# speed_controllers.net
KiCad netlist of a schematic drawn in EAGLE
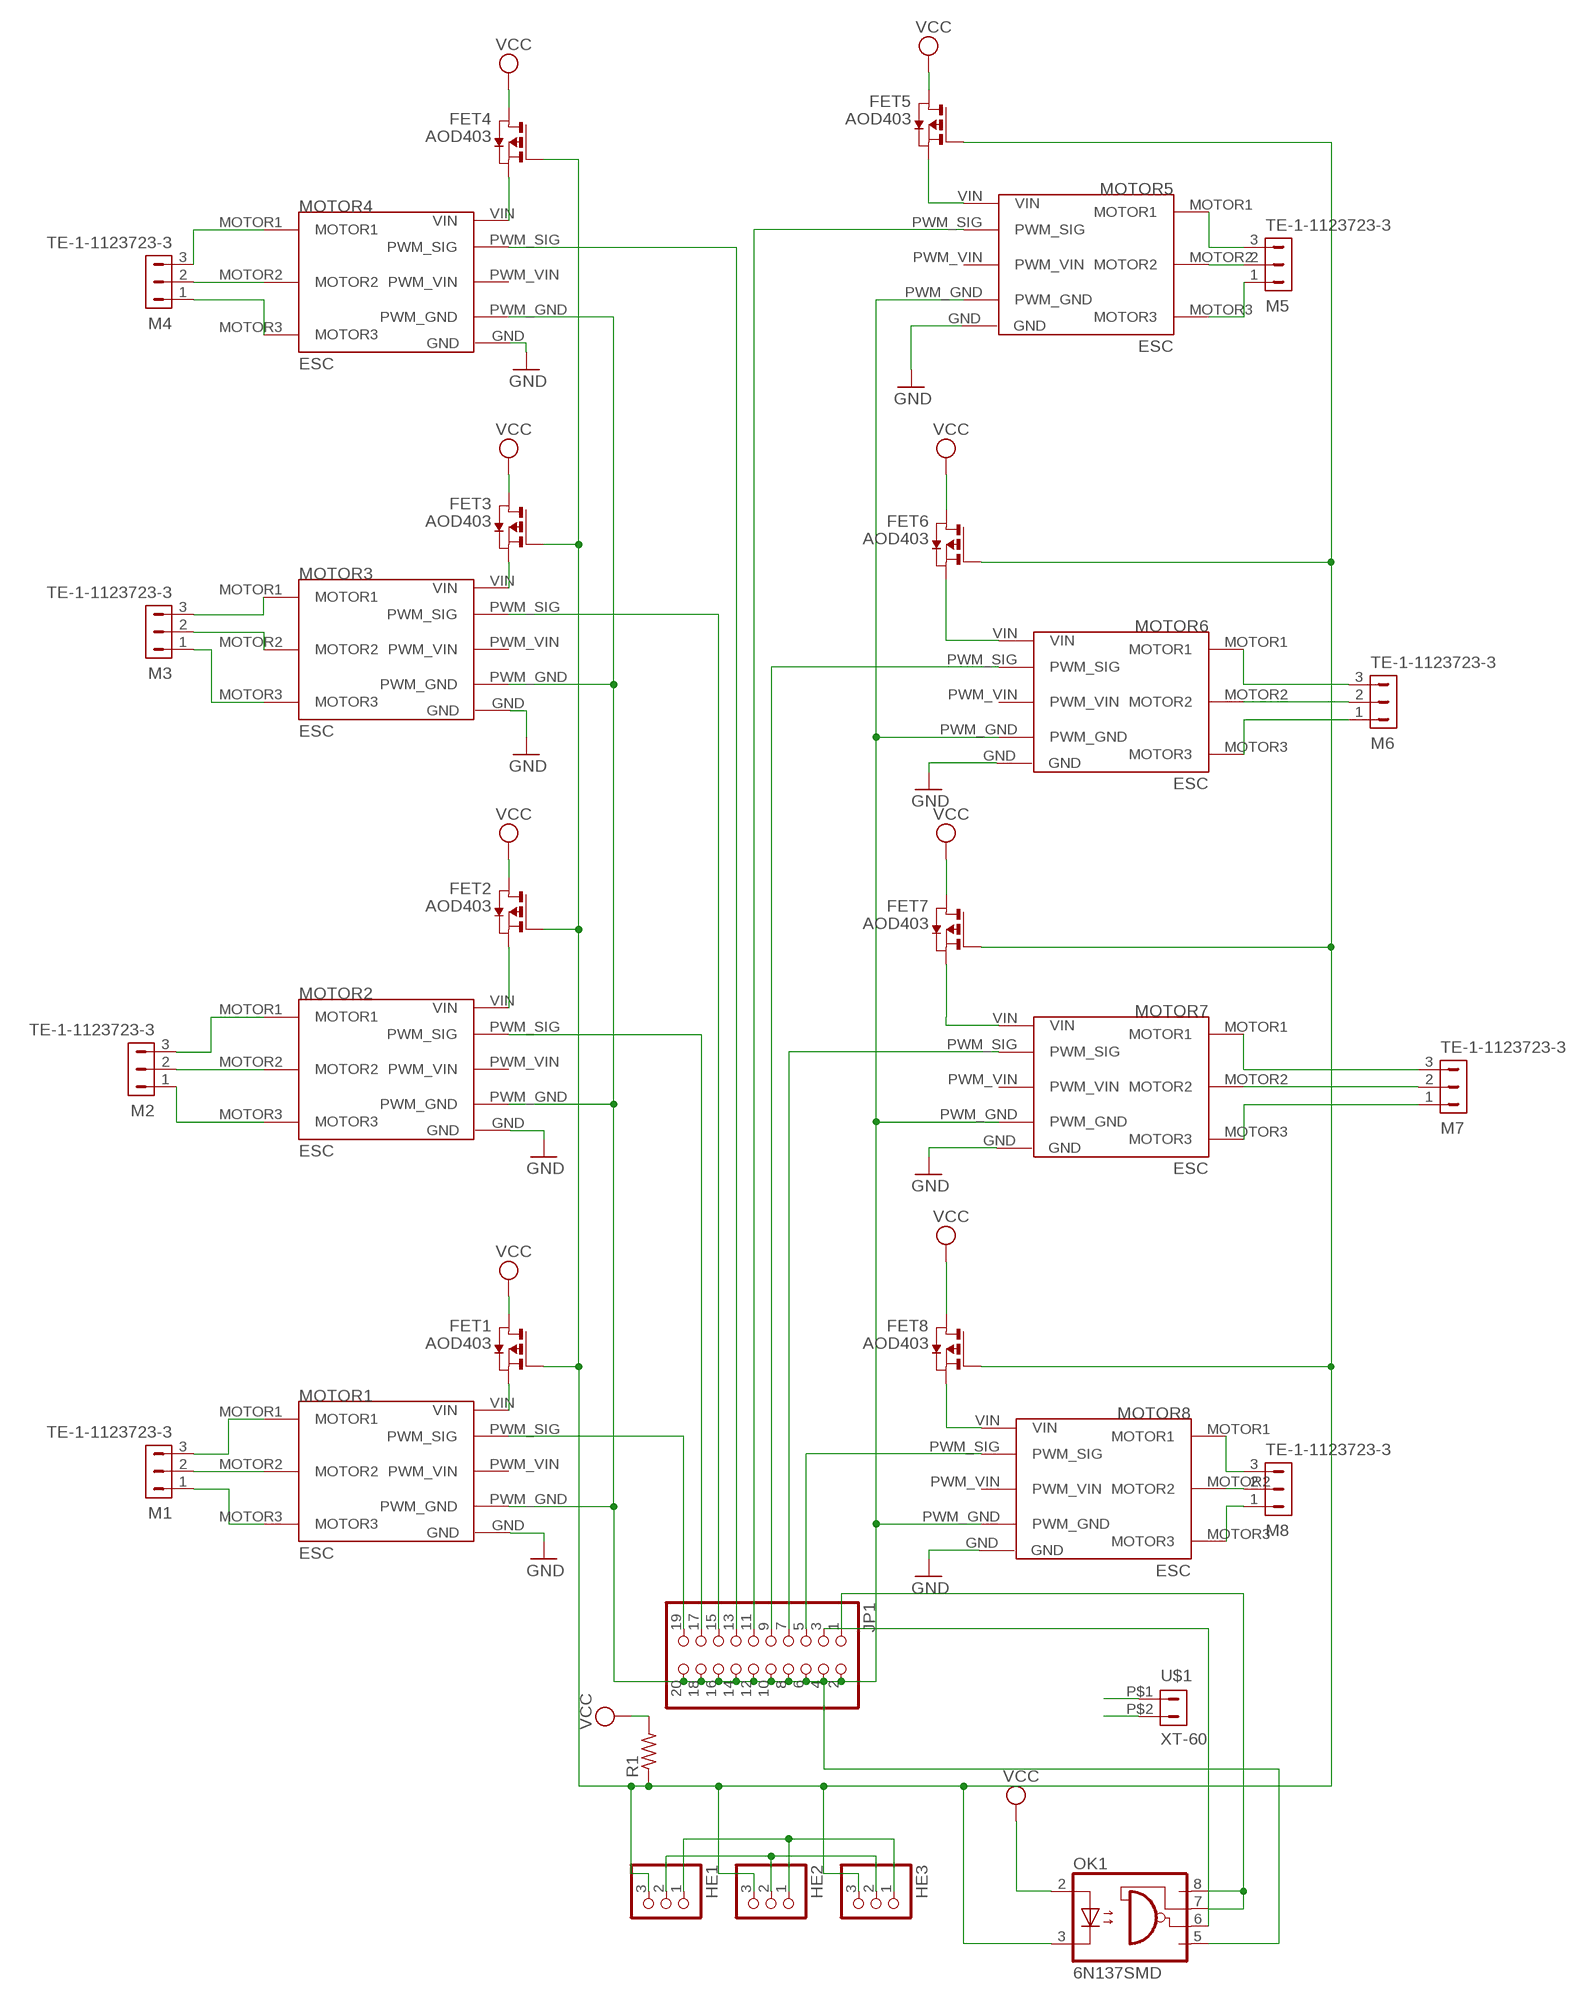
[diagram p0: schematic, sheet 1]

(export (version "E")
  (design (tool "Eeschema 10.0.6"))
  (components
    (comp (ref "FET1")
      (value "AOD403")
      (footprint "eagle-import:TO252")
      (libsource (lib "eagle-import") (part "AOD403"))
    )
    (comp (ref "FET2")
      (value "AOD403")
      (footprint "eagle-import:TO252")
      (libsource (lib "eagle-import") (part "AOD403"))
    )
    (comp (ref "FET3")
      (value "AOD403")
      (footprint "eagle-import:TO252")
      (libsource (lib "eagle-import") (part "AOD403"))
    )
    (comp (ref "FET4")
      (value "AOD403")
      (footprint "eagle-import:TO252")
      (libsource (lib "eagle-import") (part "AOD403"))
    )
    (comp (ref "FET5")
      (value "AOD403")
      (footprint "eagle-import:TO252")
      (libsource (lib "eagle-import") (part "AOD403"))
    )
    (comp (ref "FET6")
      (value "AOD403")
      (footprint "eagle-import:TO252")
      (libsource (lib "eagle-import") (part "AOD403"))
    )
    (comp (ref "FET7")
      (value "AOD403")
      (footprint "eagle-import:TO252")
      (libsource (lib "eagle-import") (part "AOD403"))
    )
    (comp (ref "FET8")
      (value "AOD403")
      (footprint "eagle-import:TO252")
      (libsource (lib "eagle-import") (part "AOD403"))
    )
    (comp (ref "HE1")
      (value "PINHD-1X3")
      (footprint "eagle-import:1X03")
      (libsource (lib "eagle-import") (part "PINHD-1X3"))
    )
    (comp (ref "HE2")
      (value "PINHD-1X3")
      (footprint "eagle-import:1X03")
      (libsource (lib "eagle-import") (part "PINHD-1X3"))
    )
    (comp (ref "HE3")
      (value "PINHD-1X3")
      (footprint "eagle-import:1X03")
      (libsource (lib "eagle-import") (part "PINHD-1X3"))
    )
    (comp (ref "JP1")
      (value "PINHD-2X10")
      (footprint "eagle-import:2X10")
      (libsource (lib "eagle-import") (part "PINHD-2X10"))
    )
    (comp (ref "M1")
      (value "TE-1-1123723-3")
      (footprint "eagle-import:TE-1-1123723-3")
      (libsource (lib "eagle-import") (part "TE-1-1123723-3"))
    )
    (comp (ref "M2")
      (value "TE-1-1123723-3")
      (footprint "eagle-import:TE-1-1123723-3")
      (libsource (lib "eagle-import") (part "TE-1-1123723-3"))
    )
    (comp (ref "M3")
      (value "TE-1-1123723-3")
      (footprint "eagle-import:TE-1-1123723-3")
      (libsource (lib "eagle-import") (part "TE-1-1123723-3"))
    )
    (comp (ref "M4")
      (value "TE-1-1123723-3")
      (footprint "eagle-import:TE-1-1123723-3")
      (libsource (lib "eagle-import") (part "TE-1-1123723-3"))
    )
    (comp (ref "M5")
      (value "TE-1-1123723-3")
      (footprint "eagle-import:TE-1-1123723-3")
      (libsource (lib "eagle-import") (part "TE-1-1123723-3"))
    )
    (comp (ref "M6")
      (value "TE-1-1123723-3")
      (footprint "eagle-import:TE-1-1123723-3")
      (libsource (lib "eagle-import") (part "TE-1-1123723-3"))
    )
    (comp (ref "M7")
      (value "TE-1-1123723-3")
      (footprint "eagle-import:TE-1-1123723-3")
      (libsource (lib "eagle-import") (part "TE-1-1123723-3"))
    )
    (comp (ref "M8")
      (value "TE-1-1123723-3")
      (footprint "eagle-import:TE-1-1123723-3")
      (libsource (lib "eagle-import") (part "TE-1-1123723-3"))
    )
    (comp (ref "MOTOR1")
      (value "ESC")
      (footprint "eagle-import:ESC")
      (libsource (lib "eagle-import") (part "ESC"))
    )
    (comp (ref "MOTOR2")
      (value "ESC")
      (footprint "eagle-import:ESC")
      (libsource (lib "eagle-import") (part "ESC"))
    )
    (comp (ref "MOTOR3")
      (value "ESC")
      (footprint "eagle-import:ESC")
      (libsource (lib "eagle-import") (part "ESC"))
    )
    (comp (ref "MOTOR4")
      (value "ESC")
      (footprint "eagle-import:ESC")
      (libsource (lib "eagle-import") (part "ESC"))
    )
    (comp (ref "MOTOR5")
      (value "ESC")
      (footprint "eagle-import:ESC")
      (libsource (lib "eagle-import") (part "ESC"))
    )
    (comp (ref "MOTOR6")
      (value "ESC")
      (footprint "eagle-import:ESC")
      (libsource (lib "eagle-import") (part "ESC"))
    )
    (comp (ref "MOTOR7")
      (value "ESC")
      (footprint "eagle-import:ESC")
      (libsource (lib "eagle-import") (part "ESC"))
    )
    (comp (ref "MOTOR8")
      (value "ESC")
      (footprint "eagle-import:ESC")
      (libsource (lib "eagle-import") (part "ESC"))
    )
    (comp (ref "OK1")
      (value "6N137SMD")
      (footprint "eagle-import:DIL8-SMD")
      (libsource (lib "eagle-import") (part "6N137SMD"))
    )
    (comp (ref "R1")
      (value "R-US_R0603")
      (footprint "eagle-import:R0603")
      (libsource (lib "eagle-import") (part "R-US_R0603"))
    )
    (comp (ref "U$1")
      (value "XT-60")
      (footprint "eagle-import:XT-60")
      (libsource (lib "eagle-import") (part "XT-60"))
    )
  )
  (nets
    (net (code "1") (name "GND") (class "Default")
      (node (ref "HE1") (pin "2") (pinfunction "2_2") (pintype "passive"))
      (node (ref "HE2") (pin "2") (pinfunction "2_2") (pintype "passive"))
      (node (ref "HE3") (pin "2") (pinfunction "2_2") (pintype "passive"))
      (node (ref "MOTOR1") (pin "GND") (pinfunction "GND_GND") (pintype "bidirectional"))
      (node (ref "MOTOR2") (pin "GND") (pinfunction "GND_GND") (pintype "bidirectional"))
      (node (ref "MOTOR3") (pin "GND") (pinfunction "GND_GND") (pintype "bidirectional"))
      (node (ref "MOTOR4") (pin "GND") (pinfunction "GND_GND") (pintype "bidirectional"))
      (node (ref "MOTOR5") (pin "GND") (pinfunction "GND_GND") (pintype "bidirectional"))
      (node (ref "MOTOR6") (pin "GND") (pinfunction "GND_GND") (pintype "bidirectional"))
      (node (ref "MOTOR7") (pin "GND") (pinfunction "GND_GND") (pintype "bidirectional"))
      (node (ref "MOTOR8") (pin "GND") (pinfunction "GND_GND") (pintype "bidirectional"))
      (node (ref "U$1") (pin "P$2") (pinfunction "2_P$2") (pintype "passive"))
    )
    (net (code "2") (name "Net-(FET1-PadS)") (class "Default")
      (node (ref "FET1") (pin "S") (pinfunction "S_S") (pintype "passive"))
      (node (ref "MOTOR1") (pin "VIN") (pinfunction "VIN_VIN") (pintype "bidirectional"))
    )
    (net (code "3") (name "Net-(FET2-PadS)") (class "Default")
      (node (ref "FET2") (pin "S") (pinfunction "S_S") (pintype "passive"))
      (node (ref "MOTOR2") (pin "VIN") (pinfunction "VIN_VIN") (pintype "bidirectional"))
    )
    (net (code "4") (name "Net-(FET3-PadS)") (class "Default")
      (node (ref "FET3") (pin "S") (pinfunction "S_S") (pintype "passive"))
      (node (ref "MOTOR3") (pin "VIN") (pinfunction "VIN_VIN") (pintype "bidirectional"))
    )
    (net (code "5") (name "Net-(FET4-PadS)") (class "Default")
      (node (ref "FET4") (pin "S") (pinfunction "S_S") (pintype "passive"))
      (node (ref "MOTOR4") (pin "VIN") (pinfunction "VIN_VIN") (pintype "bidirectional"))
    )
    (net (code "6") (name "Net-(FET5-PadS)") (class "Default")
      (node (ref "FET5") (pin "S") (pinfunction "S_S") (pintype "passive"))
      (node (ref "MOTOR5") (pin "VIN") (pinfunction "VIN_VIN") (pintype "bidirectional"))
    )
    (net (code "7") (name "Net-(FET6-PadS)") (class "Default")
      (node (ref "FET6") (pin "S") (pinfunction "S_S") (pintype "passive"))
      (node (ref "MOTOR6") (pin "VIN") (pinfunction "VIN_VIN") (pintype "bidirectional"))
    )
    (net (code "8") (name "Net-(FET7-PadS)") (class "Default")
      (node (ref "FET7") (pin "S") (pinfunction "S_S") (pintype "passive"))
      (node (ref "MOTOR7") (pin "VIN") (pinfunction "VIN_VIN") (pintype "bidirectional"))
    )
    (net (code "9") (name "Net-(FET8-PadS)") (class "Default")
      (node (ref "FET8") (pin "S") (pinfunction "S_S") (pintype "passive"))
      (node (ref "MOTOR8") (pin "VIN") (pinfunction "VIN_VIN") (pintype "bidirectional"))
    )
    (net (code "10") (name "Net-(JP1-Pad5)") (class "Default")
      (node (ref "JP1") (pin "5") (pinfunction "5_5") (pintype "passive"))
      (node (ref "MOTOR8") (pin "PWM_SIG") (pinfunction "PWM_SIG_PWM_SIG") (pintype "bidirectional"))
    )
    (net (code "11") (name "Net-(JP1-Pad7)") (class "Default")
      (node (ref "JP1") (pin "7") (pinfunction "7_7") (pintype "passive"))
      (node (ref "MOTOR7") (pin "PWM_SIG") (pinfunction "PWM_SIG_PWM_SIG") (pintype "bidirectional"))
    )
    (net (code "12") (name "Net-(JP1-Pad9)") (class "Default")
      (node (ref "JP1") (pin "9") (pinfunction "9_9") (pintype "passive"))
      (node (ref "MOTOR6") (pin "PWM_SIG") (pinfunction "PWM_SIG_PWM_SIG") (pintype "bidirectional"))
    )
    (net (code "13") (name "Net-(JP1-Pad11)") (class "Default")
      (node (ref "JP1") (pin "11") (pinfunction "11_11") (pintype "passive"))
      (node (ref "MOTOR5") (pin "PWM_SIG") (pinfunction "PWM_SIG_PWM_SIG") (pintype "bidirectional"))
    )
    (net (code "14") (name "Net-(JP1-Pad13)") (class "Default")
      (node (ref "JP1") (pin "13") (pinfunction "13_13") (pintype "passive"))
      (node (ref "MOTOR4") (pin "PWM_SIG") (pinfunction "PWM_SIG_PWM_SIG") (pintype "bidirectional"))
    )
    (net (code "15") (name "Net-(JP1-Pad15)") (class "Default")
      (node (ref "JP1") (pin "15") (pinfunction "15_15") (pintype "passive"))
      (node (ref "MOTOR3") (pin "PWM_SIG") (pinfunction "PWM_SIG_PWM_SIG") (pintype "bidirectional"))
    )
    (net (code "16") (name "Net-(JP1-Pad17)") (class "Default")
      (node (ref "JP1") (pin "17") (pinfunction "17_17") (pintype "passive"))
      (node (ref "MOTOR2") (pin "PWM_SIG") (pinfunction "PWM_SIG_PWM_SIG") (pintype "bidirectional"))
    )
    (net (code "17") (name "Net-(JP1-Pad19)") (class "Default")
      (node (ref "JP1") (pin "19") (pinfunction "19_19") (pintype "passive"))
      (node (ref "MOTOR1") (pin "PWM_SIG") (pinfunction "PWM_SIG_PWM_SIG") (pintype "bidirectional"))
    )
    (net (code "18") (name "Net-(M1-Pad1)") (class "Default")
      (node (ref "M1") (pin "1") (pinfunction "1_1") (pintype "passive"))
      (node (ref "MOTOR1") (pin "MOTOR3") (pinfunction "MOTOR3_MOTOR3") (pintype "bidirectional"))
    )
    (net (code "19") (name "Net-(M1-Pad2)") (class "Default")
      (node (ref "M1") (pin "2") (pinfunction "2_2") (pintype "passive"))
      (node (ref "MOTOR1") (pin "MOTOR2") (pinfunction "MOTOR2_MOTOR2") (pintype "bidirectional"))
    )
    (net (code "20") (name "Net-(M1-Pad3)") (class "Default")
      (node (ref "M1") (pin "3") (pinfunction "3_3") (pintype "passive"))
      (node (ref "MOTOR1") (pin "MOTOR1") (pinfunction "MOTOR1_MOTOR1") (pintype "bidirectional"))
    )
    (net (code "21") (name "Net-(M2-Pad1)") (class "Default")
      (node (ref "M2") (pin "1") (pinfunction "1_1") (pintype "passive"))
      (node (ref "MOTOR2") (pin "MOTOR3") (pinfunction "MOTOR3_MOTOR3") (pintype "bidirectional"))
    )
    (net (code "22") (name "Net-(M2-Pad2)") (class "Default")
      (node (ref "M2") (pin "2") (pinfunction "2_2") (pintype "passive"))
      (node (ref "MOTOR2") (pin "MOTOR2") (pinfunction "MOTOR2_MOTOR2") (pintype "bidirectional"))
    )
    (net (code "23") (name "Net-(M2-Pad3)") (class "Default")
      (node (ref "M2") (pin "3") (pinfunction "3_3") (pintype "passive"))
      (node (ref "MOTOR2") (pin "MOTOR1") (pinfunction "MOTOR1_MOTOR1") (pintype "bidirectional"))
    )
    (net (code "24") (name "Net-(M3-Pad1)") (class "Default")
      (node (ref "M3") (pin "1") (pinfunction "1_1") (pintype "passive"))
      (node (ref "MOTOR3") (pin "MOTOR3") (pinfunction "MOTOR3_MOTOR3") (pintype "bidirectional"))
    )
    (net (code "25") (name "Net-(M3-Pad2)") (class "Default")
      (node (ref "M3") (pin "2") (pinfunction "2_2") (pintype "passive"))
      (node (ref "MOTOR3") (pin "MOTOR2") (pinfunction "MOTOR2_MOTOR2") (pintype "bidirectional"))
    )
    (net (code "26") (name "Net-(M3-Pad3)") (class "Default")
      (node (ref "M3") (pin "3") (pinfunction "3_3") (pintype "passive"))
      (node (ref "MOTOR3") (pin "MOTOR1") (pinfunction "MOTOR1_MOTOR1") (pintype "bidirectional"))
    )
    (net (code "27") (name "Net-(M4-Pad1)") (class "Default")
      (node (ref "M4") (pin "1") (pinfunction "1_1") (pintype "passive"))
      (node (ref "MOTOR4") (pin "MOTOR3") (pinfunction "MOTOR3_MOTOR3") (pintype "bidirectional"))
    )
    (net (code "28") (name "Net-(M4-Pad2)") (class "Default")
      (node (ref "M4") (pin "2") (pinfunction "2_2") (pintype "passive"))
      (node (ref "MOTOR4") (pin "MOTOR2") (pinfunction "MOTOR2_MOTOR2") (pintype "bidirectional"))
    )
    (net (code "29") (name "Net-(M4-Pad3)") (class "Default")
      (node (ref "M4") (pin "3") (pinfunction "3_3") (pintype "passive"))
      (node (ref "MOTOR4") (pin "MOTOR1") (pinfunction "MOTOR1_MOTOR1") (pintype "bidirectional"))
    )
    (net (code "30") (name "Net-(M5-Pad1)") (class "Default")
      (node (ref "M5") (pin "1") (pinfunction "1_1") (pintype "passive"))
      (node (ref "MOTOR5") (pin "MOTOR3") (pinfunction "MOTOR3_MOTOR3") (pintype "bidirectional"))
    )
    (net (code "31") (name "Net-(M5-Pad2)") (class "Default")
      (node (ref "M5") (pin "2") (pinfunction "2_2") (pintype "passive"))
      (node (ref "MOTOR5") (pin "MOTOR2") (pinfunction "MOTOR2_MOTOR2") (pintype "bidirectional"))
    )
    (net (code "32") (name "Net-(M5-Pad3)") (class "Default")
      (node (ref "M5") (pin "3") (pinfunction "3_3") (pintype "passive"))
      (node (ref "MOTOR5") (pin "MOTOR1") (pinfunction "MOTOR1_MOTOR1") (pintype "bidirectional"))
    )
    (net (code "33") (name "Net-(M6-Pad1)") (class "Default")
      (node (ref "M6") (pin "1") (pinfunction "1_1") (pintype "passive"))
      (node (ref "MOTOR6") (pin "MOTOR3") (pinfunction "MOTOR3_MOTOR3") (pintype "bidirectional"))
    )
    (net (code "34") (name "Net-(M6-Pad2)") (class "Default")
      (node (ref "M6") (pin "2") (pinfunction "2_2") (pintype "passive"))
      (node (ref "MOTOR6") (pin "MOTOR2") (pinfunction "MOTOR2_MOTOR2") (pintype "bidirectional"))
    )
    (net (code "35") (name "Net-(M6-Pad3)") (class "Default")
      (node (ref "M6") (pin "3") (pinfunction "3_3") (pintype "passive"))
      (node (ref "MOTOR6") (pin "MOTOR1") (pinfunction "MOTOR1_MOTOR1") (pintype "bidirectional"))
    )
    (net (code "36") (name "Net-(M7-Pad1)") (class "Default")
      (node (ref "M7") (pin "1") (pinfunction "1_1") (pintype "passive"))
      (node (ref "MOTOR7") (pin "MOTOR3") (pinfunction "MOTOR3_MOTOR3") (pintype "bidirectional"))
    )
    (net (code "37") (name "Net-(M7-Pad2)") (class "Default")
      (node (ref "M7") (pin "2") (pinfunction "2_2") (pintype "passive"))
      (node (ref "MOTOR7") (pin "MOTOR2") (pinfunction "MOTOR2_MOTOR2") (pintype "bidirectional"))
    )
    (net (code "38") (name "Net-(M7-Pad3)") (class "Default")
      (node (ref "M7") (pin "3") (pinfunction "3_3") (pintype "passive"))
      (node (ref "MOTOR7") (pin "MOTOR1") (pinfunction "MOTOR1_MOTOR1") (pintype "bidirectional"))
    )
    (net (code "39") (name "Net-(M8-Pad1)") (class "Default")
      (node (ref "M8") (pin "1") (pinfunction "1_1") (pintype "passive"))
      (node (ref "MOTOR8") (pin "MOTOR3") (pinfunction "MOTOR3_MOTOR3") (pintype "bidirectional"))
    )
    (net (code "40") (name "Net-(M8-Pad2)") (class "Default")
      (node (ref "M8") (pin "2") (pinfunction "2_2") (pintype "passive"))
      (node (ref "MOTOR8") (pin "MOTOR2") (pinfunction "MOTOR2_MOTOR2") (pintype "bidirectional"))
    )
    (net (code "41") (name "Net-(M8-Pad3)") (class "Default")
      (node (ref "M8") (pin "3") (pinfunction "3_3") (pintype "passive"))
      (node (ref "MOTOR8") (pin "MOTOR1") (pinfunction "MOTOR1_MOTOR1") (pintype "bidirectional"))
    )
    (net (code "42") (name "Net-(OK1-C)") (class "Default")
      (node (ref "FET1") (pin "G") (pinfunction "G_G") (pintype "passive"))
      (node (ref "FET2") (pin "G") (pinfunction "G_G") (pintype "passive"))
      (node (ref "FET3") (pin "G") (pinfunction "G_G") (pintype "passive"))
      (node (ref "FET4") (pin "G") (pinfunction "G_G") (pintype "passive"))
      (node (ref "FET5") (pin "G") (pinfunction "G_G") (pintype "passive"))
      (node (ref "FET6") (pin "G") (pinfunction "G_G") (pintype "passive"))
      (node (ref "FET7") (pin "G") (pinfunction "G_G") (pintype "passive"))
      (node (ref "FET8") (pin "G") (pinfunction "G_G") (pintype "passive"))
      (node (ref "HE1") (pin "3") (pinfunction "3_3") (pintype "passive"))
      (node (ref "HE2") (pin "3") (pinfunction "3_3") (pintype "passive"))
      (node (ref "HE3") (pin "3") (pinfunction "3_3") (pintype "passive"))
      (node (ref "OK1") (pin "3") (pinfunction "C_3") (pintype "passive"))
      (node (ref "R1") (pin "1") (pinfunction "1_1") (pintype "passive"))
    )
    (net (code "43") (name "Net-(OK1-GND)") (class "Default")
      (node (ref "JP1") (pin "10") (pinfunction "10_10") (pintype "passive"))
      (node (ref "JP1") (pin "12") (pinfunction "12_12") (pintype "passive"))
      (node (ref "JP1") (pin "14") (pinfunction "14_14") (pintype "passive"))
      (node (ref "JP1") (pin "16") (pinfunction "16_16") (pintype "passive"))
      (node (ref "JP1") (pin "18") (pinfunction "18_18") (pintype "passive"))
      (node (ref "JP1") (pin "2") (pinfunction "2_2") (pintype "passive"))
      (node (ref "JP1") (pin "20") (pinfunction "20_20") (pintype "passive"))
      (node (ref "JP1") (pin "4") (pinfunction "4_4") (pintype "passive"))
      (node (ref "JP1") (pin "6") (pinfunction "6_6") (pintype "passive"))
      (node (ref "JP1") (pin "8") (pinfunction "8_8") (pintype "passive"))
      (node (ref "MOTOR1") (pin "PWM_GND") (pinfunction "PWM_GND_PWM_GND") (pintype "bidirectional"))
      (node (ref "MOTOR2") (pin "PWM_GND") (pinfunction "PWM_GND_PWM_GND") (pintype "bidirectional"))
      (node (ref "MOTOR3") (pin "PWM_GND") (pinfunction "PWM_GND_PWM_GND") (pintype "bidirectional"))
      (node (ref "MOTOR4") (pin "PWM_GND") (pinfunction "PWM_GND_PWM_GND") (pintype "bidirectional"))
      (node (ref "MOTOR5") (pin "PWM_GND") (pinfunction "PWM_GND_PWM_GND") (pintype "bidirectional"))
      (node (ref "MOTOR6") (pin "PWM_GND") (pinfunction "PWM_GND_PWM_GND") (pintype "bidirectional"))
      (node (ref "MOTOR7") (pin "PWM_GND") (pinfunction "PWM_GND_PWM_GND") (pintype "bidirectional"))
      (node (ref "MOTOR8") (pin "PWM_GND") (pinfunction "PWM_GND_PWM_GND") (pintype "bidirectional"))
      (node (ref "OK1") (pin "5") (pinfunction "GND_5") (pintype "passive"))
    )
    (net (code "44") (name "Net-(OK1-VCC)") (class "Default")
      (node (ref "JP1") (pin "1") (pinfunction "1_1") (pintype "passive"))
      (node (ref "OK1") (pin "7") (pinfunction "VE_7") (pintype "passive"))
      (node (ref "OK1") (pin "8") (pinfunction "VCC_8") (pintype "passive"))
    )
    (net (code "45") (name "Net-(OK1-VO)") (class "Default")
      (node (ref "JP1") (pin "3") (pinfunction "3_3") (pintype "passive"))
      (node (ref "OK1") (pin "6") (pinfunction "VO_6") (pintype "passive"))
    )
    (net (code "46") (name "VCC") (class "Default")
      (node (ref "FET1") (pin "D") (pinfunction "D_D") (pintype "passive"))
      (node (ref "FET2") (pin "D") (pinfunction "D_D") (pintype "passive"))
      (node (ref "FET3") (pin "D") (pinfunction "D_D") (pintype "passive"))
      (node (ref "FET4") (pin "D") (pinfunction "D_D") (pintype "passive"))
      (node (ref "FET5") (pin "D") (pinfunction "D_D") (pintype "passive"))
      (node (ref "FET6") (pin "D") (pinfunction "D_D") (pintype "passive"))
      (node (ref "FET7") (pin "D") (pinfunction "D_D") (pintype "passive"))
      (node (ref "FET8") (pin "D") (pinfunction "D_D") (pintype "passive"))
      (node (ref "HE1") (pin "1") (pinfunction "1_1") (pintype "passive"))
      (node (ref "HE2") (pin "1") (pinfunction "1_1") (pintype "passive"))
      (node (ref "HE3") (pin "1") (pinfunction "1_1") (pintype "passive"))
      (node (ref "OK1") (pin "2") (pinfunction "A_2") (pintype "passive"))
      (node (ref "R1") (pin "2") (pinfunction "2_2") (pintype "passive"))
      (node (ref "U$1") (pin "P$1") (pinfunction "1_P$1") (pintype "passive"))
    )
    (net (code "47") (name "unconnected-(MOTOR1-PadPWM_VIN)") (class "Default")
      (node (ref "MOTOR1") (pin "PWM_VIN") (pinfunction "PWM_VIN_PWM_VIN") (pintype "bidirectional"))
    )
    (net (code "48") (name "unconnected-(MOTOR2-PadPWM_VIN)") (class "Default")
      (node (ref "MOTOR2") (pin "PWM_VIN") (pinfunction "PWM_VIN_PWM_VIN") (pintype "bidirectional"))
    )
    (net (code "49") (name "unconnected-(MOTOR3-PadPWM_VIN)") (class "Default")
      (node (ref "MOTOR3") (pin "PWM_VIN") (pinfunction "PWM_VIN_PWM_VIN") (pintype "bidirectional"))
    )
    (net (code "50") (name "unconnected-(MOTOR4-PadPWM_VIN)") (class "Default")
      (node (ref "MOTOR4") (pin "PWM_VIN") (pinfunction "PWM_VIN_PWM_VIN") (pintype "bidirectional"))
    )
    (net (code "51") (name "unconnected-(MOTOR5-PadPWM_VIN)") (class "Default")
      (node (ref "MOTOR5") (pin "PWM_VIN") (pinfunction "PWM_VIN_PWM_VIN") (pintype "bidirectional"))
    )
    (net (code "52") (name "unconnected-(MOTOR6-PadPWM_VIN)") (class "Default")
      (node (ref "MOTOR6") (pin "PWM_VIN") (pinfunction "PWM_VIN_PWM_VIN") (pintype "bidirectional"))
    )
    (net (code "53") (name "unconnected-(MOTOR7-PadPWM_VIN)") (class "Default")
      (node (ref "MOTOR7") (pin "PWM_VIN") (pinfunction "PWM_VIN_PWM_VIN") (pintype "bidirectional"))
    )
    (net (code "54") (name "unconnected-(MOTOR8-PadPWM_VIN)") (class "Default")
      (node (ref "MOTOR8") (pin "PWM_VIN") (pinfunction "PWM_VIN_PWM_VIN") (pintype "bidirectional"))
    )
  )
)
